# so2walker.net
KiCad netlist of a schematic drawn in EAGLE
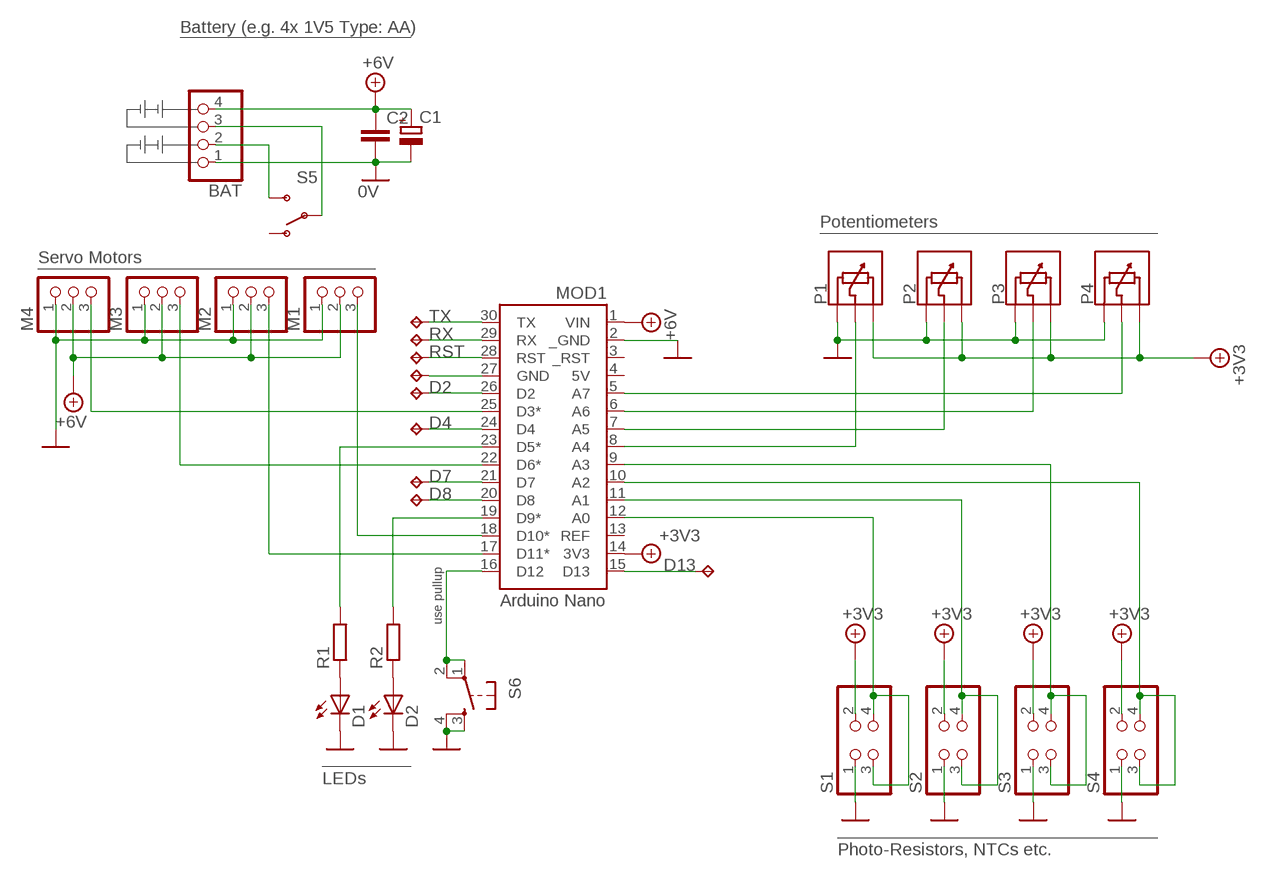
[diagram p0: schematic, sheet 1]

(export (version "E")
  (design (tool "Eeschema 10.0.6"))
  (components
    (comp (ref "BAT")
      (value "PINHD-1X04_2.54-S")
      (footprint "eagle-import:1X04-S")
      (libsource (lib "eagle-import") (part "PINHD-1X04_2.54-S"))
    )
    (comp (ref "C1")
      (value "CPOL-EUE3.5-8")
      (footprint "eagle-import:E3,5-8")
      (libsource (lib "eagle-import") (part "CPOL-EUE3.5-8"))
    )
    (comp (ref "C2")
      (value "C-EU025-025X050")
      (footprint "eagle-import:C025-025X050")
      (libsource (lib "eagle-import") (part "C-EU025-025X050"))
    )
    (comp (ref "D1")
      (value "LED3MM")
      (footprint "eagle-import:LED3MM")
      (libsource (lib "eagle-import") (part "LED3MM"))
    )
    (comp (ref "D2")
      (value "LED3MM")
      (footprint "eagle-import:LED3MM")
      (libsource (lib "eagle-import") (part "LED3MM"))
    )
    (comp (ref "M1")
      (value "PINHD-1X03_2.54-S")
      (footprint "eagle-import:1X03-S")
      (libsource (lib "eagle-import") (part "PINHD-1X03_2.54-S"))
    )
    (comp (ref "M2")
      (value "PINHD-1X03_2.54-S")
      (footprint "eagle-import:1X03-S")
      (libsource (lib "eagle-import") (part "PINHD-1X03_2.54-S"))
    )
    (comp (ref "M3")
      (value "PINHD-1X03_2.54-S")
      (footprint "eagle-import:1X03-S")
      (libsource (lib "eagle-import") (part "PINHD-1X03_2.54-S"))
    )
    (comp (ref "M4")
      (value "PINHD-1X03_2.54-S")
      (footprint "eagle-import:1X03-S")
      (libsource (lib "eagle-import") (part "PINHD-1X03_2.54-S"))
    )
    (comp (ref "MOD1")
      (value "Arduino Nano")
      (footprint "eagle-import:NANOSHLD_INV")
      (libsource (lib "eagle-import") (part "ARDUINO_NANO_SHLD'INVERSE'"))
    )
    (comp (ref "P1")
      (value "TRIMPOT_UNIV")
      (footprint "eagle-import:UNIPOT_DIL")
      (libsource (lib "eagle-import") (part "TRIMPOT_UNIV"))
    )
    (comp (ref "P2")
      (value "TRIMPOT_UNIV")
      (footprint "eagle-import:UNIPOT_DIL")
      (libsource (lib "eagle-import") (part "TRIMPOT_UNIV"))
    )
    (comp (ref "P3")
      (value "TRIMPOT_UNIV")
      (footprint "eagle-import:UNIPOT_DIL")
      (libsource (lib "eagle-import") (part "TRIMPOT_UNIV"))
    )
    (comp (ref "P4")
      (value "TRIMPOT_UNIV")
      (footprint "eagle-import:UNIPOT_DIL")
      (libsource (lib "eagle-import") (part "TRIMPOT_UNIV"))
    )
    (comp (ref "R1")
      (value "R-EU_0207/7")
      (footprint "eagle-import:0207_7")
      (libsource (lib "eagle-import") (part "R-EU_0207/7"))
    )
    (comp (ref "R2")
      (value "R-EU_0207/7")
      (footprint "eagle-import:0207_7")
      (libsource (lib "eagle-import") (part "R-EU_0207/7"))
    )
    (comp (ref "S1")
      (value "PINHD-2X02_2.54")
      (footprint "eagle-import:2X02")
      (libsource (lib "eagle-import") (part "PINHD-2X02_2.54"))
    )
    (comp (ref "S2")
      (value "PINHD-2X02_2.54")
      (footprint "eagle-import:2X02")
      (libsource (lib "eagle-import") (part "PINHD-2X02_2.54"))
    )
    (comp (ref "S3")
      (value "PINHD-2X02_2.54")
      (footprint "eagle-import:2X02")
      (libsource (lib "eagle-import") (part "PINHD-2X02_2.54"))
    )
    (comp (ref "S4")
      (value "PINHD-2X02_2.54")
      (footprint "eagle-import:2X02")
      (libsource (lib "eagle-import") (part "PINHD-2X02_2.54"))
    )
    (comp (ref "S5")
      (value "SWITCH-SPSTPTH")
      (footprint "eagle-import:SWITCH-SPDT")
      (libsource (lib "eagle-import") (part "SWITCH-SPSTPTH"))
    )
    (comp (ref "S6")
      (value "TAC_SWITCHPTH")
      (footprint "eagle-import:TACTILE-PTH")
      (libsource (lib "eagle-import") (part "TAC_SWITCHPTH"))
    )
    (comp (ref "TP1")
      (value "TPB1,27")
      (footprint "eagle-import:B1,27")
      (libsource (lib "eagle-import") (part "TPB1,27"))
    )
    (comp (ref "TP2")
      (value "TPB1,27")
      (footprint "eagle-import:B1,27")
      (libsource (lib "eagle-import") (part "TPB1,27"))
    )
    (comp (ref "TP3")
      (value "TPB1,27")
      (footprint "eagle-import:B1,27")
      (libsource (lib "eagle-import") (part "TPB1,27"))
    )
    (comp (ref "TP4")
      (value "TPB1,27")
      (footprint "eagle-import:B1,27")
      (libsource (lib "eagle-import") (part "TPB1,27"))
    )
    (comp (ref "TP5")
      (value "TPB1,27")
      (footprint "eagle-import:B1,27")
      (libsource (lib "eagle-import") (part "TPB1,27"))
    )
    (comp (ref "TP6")
      (value "TPB1,27")
      (footprint "eagle-import:B1,27")
      (libsource (lib "eagle-import") (part "TPB1,27"))
    )
    (comp (ref "TP7")
      (value "TPB1,27")
      (footprint "eagle-import:B1,27")
      (libsource (lib "eagle-import") (part "TPB1,27"))
    )
    (comp (ref "TP8")
      (value "TPB1,27")
      (footprint "eagle-import:B1,27")
      (libsource (lib "eagle-import") (part "TPB1,27"))
    )
    (comp (ref "TP10")
      (value "TPB1,27")
      (footprint "eagle-import:B1,27")
      (libsource (lib "eagle-import") (part "TPB1,27"))
    )
  )
  (nets
    (net (code "1") (name "+3V3") (class "Default")
      (node (ref "BAT") (pin "4") (pinfunction "4_4") (pintype "passive"))
      (node (ref "C1") (pin "+") (pinfunction "+_+") (pintype "passive"))
      (node (ref "C2") (pin "1") (pinfunction "1_1") (pintype "passive"))
      (node (ref "M1") (pin "2") (pinfunction "2_2") (pintype "passive"))
      (node (ref "M2") (pin "2") (pinfunction "2_2") (pintype "passive"))
      (node (ref "M3") (pin "2") (pinfunction "2_2") (pintype "passive"))
      (node (ref "M4") (pin "2") (pinfunction "2_2") (pintype "passive"))
      (node (ref "MOD1") (pin "1") (pinfunction "VIN_1") (pintype "power_in"))
      (node (ref "MOD1") (pin "14") (pinfunction "3V3_14") (pintype "power_in"))
      (node (ref "P1") (pin "3A") (pinfunction "P$3_3A") (pintype "bidirectional"))
      (node (ref "P1") (pin "3B") (pinfunction "P$3_3B") (pintype "bidirectional"))
      (node (ref "P2") (pin "3A") (pinfunction "P$3_3A") (pintype "bidirectional"))
      (node (ref "P2") (pin "3B") (pinfunction "P$3_3B") (pintype "bidirectional"))
      (node (ref "P3") (pin "3A") (pinfunction "P$3_3A") (pintype "bidirectional"))
      (node (ref "P3") (pin "3B") (pinfunction "P$3_3B") (pintype "bidirectional"))
      (node (ref "P4") (pin "3A") (pinfunction "P$3_3A") (pintype "bidirectional"))
      (node (ref "P4") (pin "3B") (pinfunction "P$3_3B") (pintype "bidirectional"))
      (node (ref "S1") (pin "2") (pinfunction "2_2") (pintype "passive"))
      (node (ref "S2") (pin "2") (pinfunction "2_2") (pintype "passive"))
      (node (ref "S3") (pin "2") (pinfunction "2_2") (pintype "passive"))
      (node (ref "S4") (pin "2") (pinfunction "2_2") (pintype "passive"))
    )
    (net (code "2") (name "/5V") (class "Default")
      (node (ref "MOD1") (pin "4") (pinfunction "5V_4") (pintype "power_in"))
    )
    (net (code "3") (name "/D2") (class "Default")
      (node (ref "MOD1") (pin "26") (pinfunction "D2_26") (pintype "bidirectional"))
      (node (ref "TP4") (pin "TP") (pinfunction "TP_TP") (pintype "input"))
    )
    (net (code "4") (name "/D4") (class "Default")
      (node (ref "MOD1") (pin "24") (pinfunction "D4_24") (pintype "bidirectional"))
      (node (ref "TP5") (pin "TP") (pinfunction "TP_TP") (pintype "input"))
    )
    (net (code "5") (name "/D7") (class "Default")
      (node (ref "MOD1") (pin "21") (pinfunction "D7_21") (pintype "bidirectional"))
      (node (ref "TP6") (pin "TP") (pinfunction "TP_TP") (pintype "input"))
    )
    (net (code "6") (name "/D8") (class "Default")
      (node (ref "MOD1") (pin "20") (pinfunction "D8_20") (pintype "bidirectional"))
      (node (ref "TP7") (pin "TP") (pinfunction "TP_TP") (pintype "input"))
    )
    (net (code "7") (name "/D13") (class "Default")
      (node (ref "MOD1") (pin "15") (pinfunction "D13_15") (pintype "bidirectional"))
      (node (ref "TP8") (pin "TP") (pinfunction "TP_TP") (pintype "input"))
    )
    (net (code "8") (name "/REF") (class "Default")
      (node (ref "MOD1") (pin "13") (pinfunction "REF_13") (pintype "power_in"))
    )
    (net (code "9") (name "/RST") (class "Default")
      (node (ref "MOD1") (pin "28") (pinfunction "RST_28") (pintype "input"))
      (node (ref "TP3") (pin "TP") (pinfunction "TP_TP") (pintype "input"))
    )
    (net (code "10") (name "/RX") (class "Default")
      (node (ref "MOD1") (pin "29") (pinfunction "RX_29") (pintype "bidirectional"))
      (node (ref "TP2") (pin "TP") (pinfunction "TP_TP") (pintype "input"))
    )
    (net (code "11") (name "/TX") (class "Default")
      (node (ref "MOD1") (pin "30") (pinfunction "TX_30") (pintype "bidirectional"))
      (node (ref "TP1") (pin "TP") (pinfunction "TP_TP") (pintype "input"))
    )
    (net (code "12") (name "0V") (class "Default")
      (node (ref "BAT") (pin "1") (pinfunction "1_1") (pintype "passive"))
      (node (ref "C1") (pin "-") (pinfunction "-_-") (pintype "passive"))
      (node (ref "C2") (pin "2") (pinfunction "2_2") (pintype "passive"))
      (node (ref "D1") (pin "K") (pinfunction "C_K") (pintype "passive"))
      (node (ref "D2") (pin "K") (pinfunction "C_K") (pintype "passive"))
      (node (ref "M1") (pin "1") (pinfunction "1_1") (pintype "passive"))
      (node (ref "M2") (pin "1") (pinfunction "1_1") (pintype "passive"))
      (node (ref "M3") (pin "1") (pinfunction "1_1") (pintype "passive"))
      (node (ref "M4") (pin "1") (pinfunction "1_1") (pintype "passive"))
      (node (ref "MOD1") (pin "2") (pinfunction "_GND_2") (pintype "power_in"))
      (node (ref "P1") (pin "1A") (pinfunction "P$1_1A") (pintype "bidirectional"))
      (node (ref "P1") (pin "1B") (pinfunction "P$1_1B") (pintype "bidirectional"))
      (node (ref "P2") (pin "1A") (pinfunction "P$1_1A") (pintype "bidirectional"))
      (node (ref "P2") (pin "1B") (pinfunction "P$1_1B") (pintype "bidirectional"))
      (node (ref "P3") (pin "1A") (pinfunction "P$1_1A") (pintype "bidirectional"))
      (node (ref "P3") (pin "1B") (pinfunction "P$1_1B") (pintype "bidirectional"))
      (node (ref "P4") (pin "1A") (pinfunction "P$1_1A") (pintype "bidirectional"))
      (node (ref "P4") (pin "1B") (pinfunction "P$1_1B") (pintype "bidirectional"))
      (node (ref "S1") (pin "1") (pinfunction "1_1") (pintype "passive"))
      (node (ref "S2") (pin "1") (pinfunction "1_1") (pintype "passive"))
      (node (ref "S3") (pin "1") (pinfunction "1_1") (pintype "passive"))
      (node (ref "S4") (pin "1") (pinfunction "1_1") (pintype "passive"))
      (node (ref "S6") (pin "3") (pinfunction "3_3") (pintype "passive"))
      (node (ref "S6") (pin "4") (pinfunction "4_4") (pintype "passive"))
    )
    (net (code "13") (name "Net-(D1-PadA)") (class "Default")
      (node (ref "D1") (pin "A") (pinfunction "A_A") (pintype "passive"))
      (node (ref "R1") (pin "1") (pinfunction "1_1") (pintype "passive"))
    )
    (net (code "14") (name "Net-(D2-PadA)") (class "Default")
      (node (ref "D2") (pin "A") (pinfunction "A_A") (pintype "passive"))
      (node (ref "R2") (pin "1") (pinfunction "1_1") (pintype "passive"))
    )
    (net (code "15") (name "Net-(MOD1-A0)") (class "Default")
      (node (ref "MOD1") (pin "12") (pinfunction "A0_12") (pintype "bidirectional"))
      (node (ref "S1") (pin "3") (pinfunction "3_3") (pintype "passive"))
      (node (ref "S1") (pin "4") (pinfunction "4_4") (pintype "passive"))
    )
    (net (code "16") (name "Net-(MOD1-A1)") (class "Default")
      (node (ref "MOD1") (pin "11") (pinfunction "A1_11") (pintype "bidirectional"))
      (node (ref "S2") (pin "3") (pinfunction "3_3") (pintype "passive"))
      (node (ref "S2") (pin "4") (pinfunction "4_4") (pintype "passive"))
    )
    (net (code "17") (name "Net-(MOD1-A2)") (class "Default")
      (node (ref "MOD1") (pin "10") (pinfunction "A2_10") (pintype "bidirectional"))
      (node (ref "S4") (pin "3") (pinfunction "3_3") (pintype "passive"))
      (node (ref "S4") (pin "4") (pinfunction "4_4") (pintype "passive"))
    )
    (net (code "18") (name "Net-(MOD1-A3)") (class "Default")
      (node (ref "MOD1") (pin "9") (pinfunction "A3_9") (pintype "bidirectional"))
      (node (ref "S3") (pin "3") (pinfunction "3_3") (pintype "passive"))
      (node (ref "S3") (pin "4") (pinfunction "4_4") (pintype "passive"))
    )
    (net (code "19") (name "Net-(MOD1-A4)") (class "Default")
      (node (ref "MOD1") (pin "8") (pinfunction "A4_8") (pintype "bidirectional"))
      (node (ref "P1") (pin "2A") (pinfunction "P$2_2A") (pintype "bidirectional"))
      (node (ref "P1") (pin "2B") (pinfunction "P$2_2B") (pintype "bidirectional"))
    )
    (net (code "20") (name "Net-(MOD1-A5)") (class "Default")
      (node (ref "MOD1") (pin "7") (pinfunction "A5_7") (pintype "bidirectional"))
      (node (ref "P2") (pin "2A") (pinfunction "P$2_2A") (pintype "bidirectional"))
      (node (ref "P2") (pin "2B") (pinfunction "P$2_2B") (pintype "bidirectional"))
    )
    (net (code "21") (name "Net-(MOD1-A6)") (class "Default")
      (node (ref "MOD1") (pin "6") (pinfunction "A6_6") (pintype "bidirectional"))
      (node (ref "P3") (pin "2A") (pinfunction "P$2_2A") (pintype "bidirectional"))
      (node (ref "P3") (pin "2B") (pinfunction "P$2_2B") (pintype "bidirectional"))
    )
    (net (code "22") (name "Net-(MOD1-A7)") (class "Default")
      (node (ref "MOD1") (pin "5") (pinfunction "A7_5") (pintype "bidirectional"))
      (node (ref "P4") (pin "2A") (pinfunction "P$2_2A") (pintype "bidirectional"))
      (node (ref "P4") (pin "2B") (pinfunction "P$2_2B") (pintype "bidirectional"))
    )
    (net (code "23") (name "Net-(MOD1-D3*)") (class "Default")
      (node (ref "M4") (pin "3") (pinfunction "3_3") (pintype "passive"))
      (node (ref "MOD1") (pin "25") (pinfunction "D3*_25") (pintype "bidirectional"))
    )
    (net (code "24") (name "Net-(MOD1-D5*)") (class "Default")
      (node (ref "MOD1") (pin "23") (pinfunction "D5*_23") (pintype "bidirectional"))
      (node (ref "R1") (pin "2") (pinfunction "2_2") (pintype "passive"))
    )
    (net (code "25") (name "Net-(MOD1-D6*)") (class "Default")
      (node (ref "M3") (pin "3") (pinfunction "3_3") (pintype "passive"))
      (node (ref "MOD1") (pin "22") (pinfunction "D6*_22") (pintype "bidirectional"))
    )
    (net (code "26") (name "Net-(MOD1-D9*)") (class "Default")
      (node (ref "MOD1") (pin "19") (pinfunction "D9*_19") (pintype "bidirectional"))
      (node (ref "R2") (pin "2") (pinfunction "2_2") (pintype "passive"))
    )
    (net (code "27") (name "Net-(MOD1-D10*)") (class "Default")
      (node (ref "M1") (pin "3") (pinfunction "3_3") (pintype "passive"))
      (node (ref "MOD1") (pin "18") (pinfunction "D10*_18") (pintype "bidirectional"))
    )
    (net (code "28") (name "Net-(MOD1-D11*)") (class "Default")
      (node (ref "M2") (pin "3") (pinfunction "3_3") (pintype "passive"))
      (node (ref "MOD1") (pin "17") (pinfunction "D11*_17") (pintype "bidirectional"))
    )
    (net (code "29") (name "Net-(MOD1-D12)") (class "Default")
      (node (ref "MOD1") (pin "16") (pinfunction "D12_16") (pintype "bidirectional"))
      (node (ref "S6") (pin "1") (pinfunction "1_1") (pintype "passive"))
      (node (ref "S6") (pin "2") (pinfunction "2_2") (pintype "passive"))
    )
    (net (code "30") (name "Net-(MOD1-GND)") (class "Default")
      (node (ref "MOD1") (pin "27") (pinfunction "GND_27") (pintype "power_in"))
      (node (ref "TP10") (pin "TP") (pinfunction "TP_TP") (pintype "input"))
    )
    (net (code "31") (name "Net-(S5-P)") (class "Default")
      (node (ref "BAT") (pin "3") (pinfunction "3_3") (pintype "passive"))
      (node (ref "S5") (pin "2") (pinfunction "P_2") (pintype "passive"))
    )
    (net (code "32") (name "Net-(S5-S)") (class "Default")
      (node (ref "BAT") (pin "2") (pinfunction "2_2") (pintype "passive"))
      (node (ref "S5") (pin "3") (pinfunction "S_3") (pintype "passive"))
    )
    (net (code "33") (name "unconnected-(MOD1-_RST-Pad3)") (class "Default")
      (node (ref "MOD1") (pin "3") (pinfunction "_RST_3") (pintype "input"))
    )
    (net (code "34") (name "unconnected-(S5-O-Pad1)") (class "Default")
      (node (ref "S5") (pin "1") (pinfunction "O_1") (pintype "passive"))
    )
  )
)
